# Air_Control.net
KiCad netlist of a schematic drawn in Altium Designer
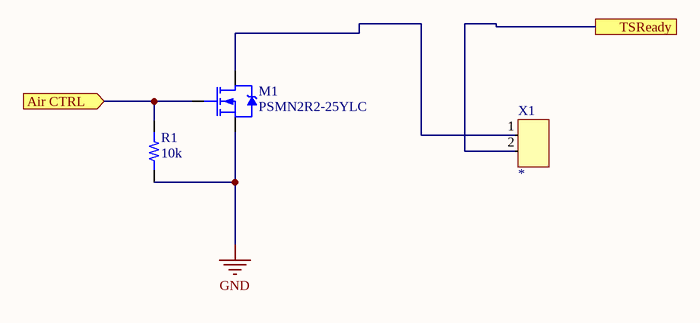
[diagram p0: Air Control.SchDoc]

(export (version "E")
  (design (tool "Eeschema 10.0.6"))
  (components
    (comp (ref "M1")
      (value "PSMN2R2-25YLC")
      (footprint "POWER-SO8")
      (description "N-Channel 25V 100A (Tc) 106W (Tc) Surface Mount LFPAK56, Power-SO8")
      (libsource (lib "altlib") (part "PSMN2R2-25YLC"))
    )
    (comp (ref "R1")
      (value "10k")
      (footprint "RES 0603/1608")
      (fields (field (name "RESISTANCE") "10k"))
      (libsource (lib "altlib") (part "Resistor"))
    )
    (comp (ref "X1")
      (value "*")
      (footprint "CONN 43650-0200 MOLEX 2PIN")
      (description "Molex 43650_0200")
      (libsource (lib "altlib") (part "CONN 2POS"))
    )
  )
  (nets
    (net (code "1") (name "/Air CTRL") (class "Default")
      (node (ref "M1") (pin "G") (pinfunction "Gate_G") (pintype "passive"))
      (node (ref "R1") (pin "2") (pinfunction "2_2") (pintype "passive"))
    )
    (net (code "2") (name "/TSReady") (class "Default") (node (ref "X1") (pin "2") (pintype "passive")))
    (net (code "3") (name "GND") (class "Default")
      (node (ref "M1") (pin "S") (pinfunction "Source_S") (pintype "passive"))
      (node (ref "R1") (pin "1") (pinfunction "1_1") (pintype "passive"))
    )
    (net (code "4") (name "Net-(M1-Drain)") (class "Default")
      (node (ref "M1") (pin "D") (pinfunction "Drain_D") (pintype "passive"))
      (node (ref "X1") (pin "1") (pintype "passive"))
    )
  )
)
